# mainBoard.net
KiCad netlist of a schematic drawn in Altium Designer
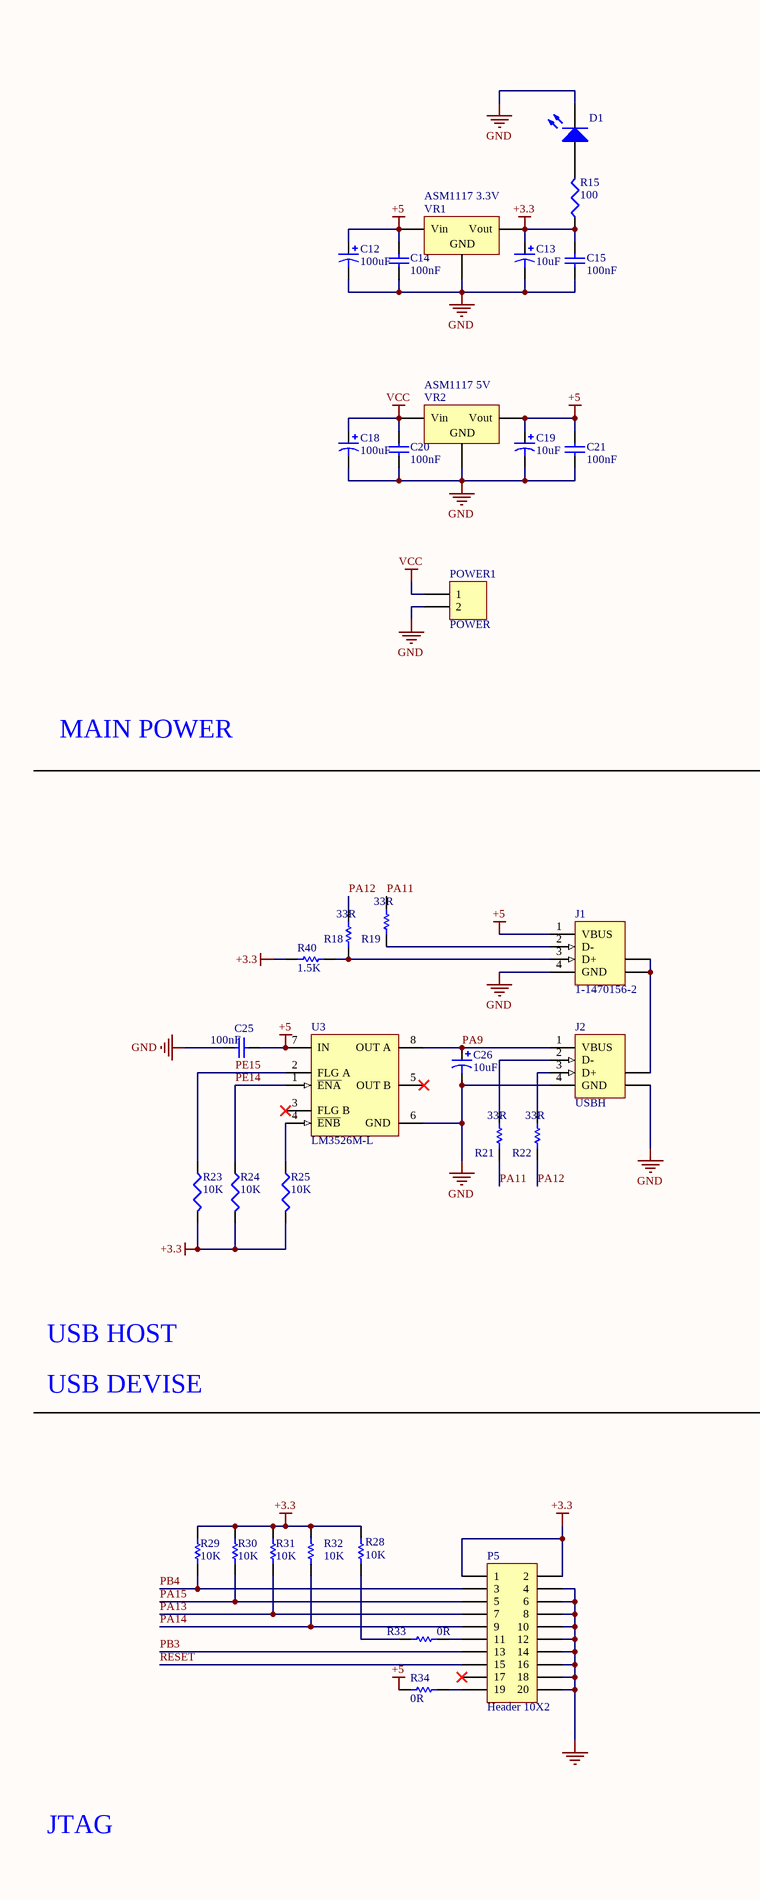
[diagram p0: mainBoard.SchDoc, left]
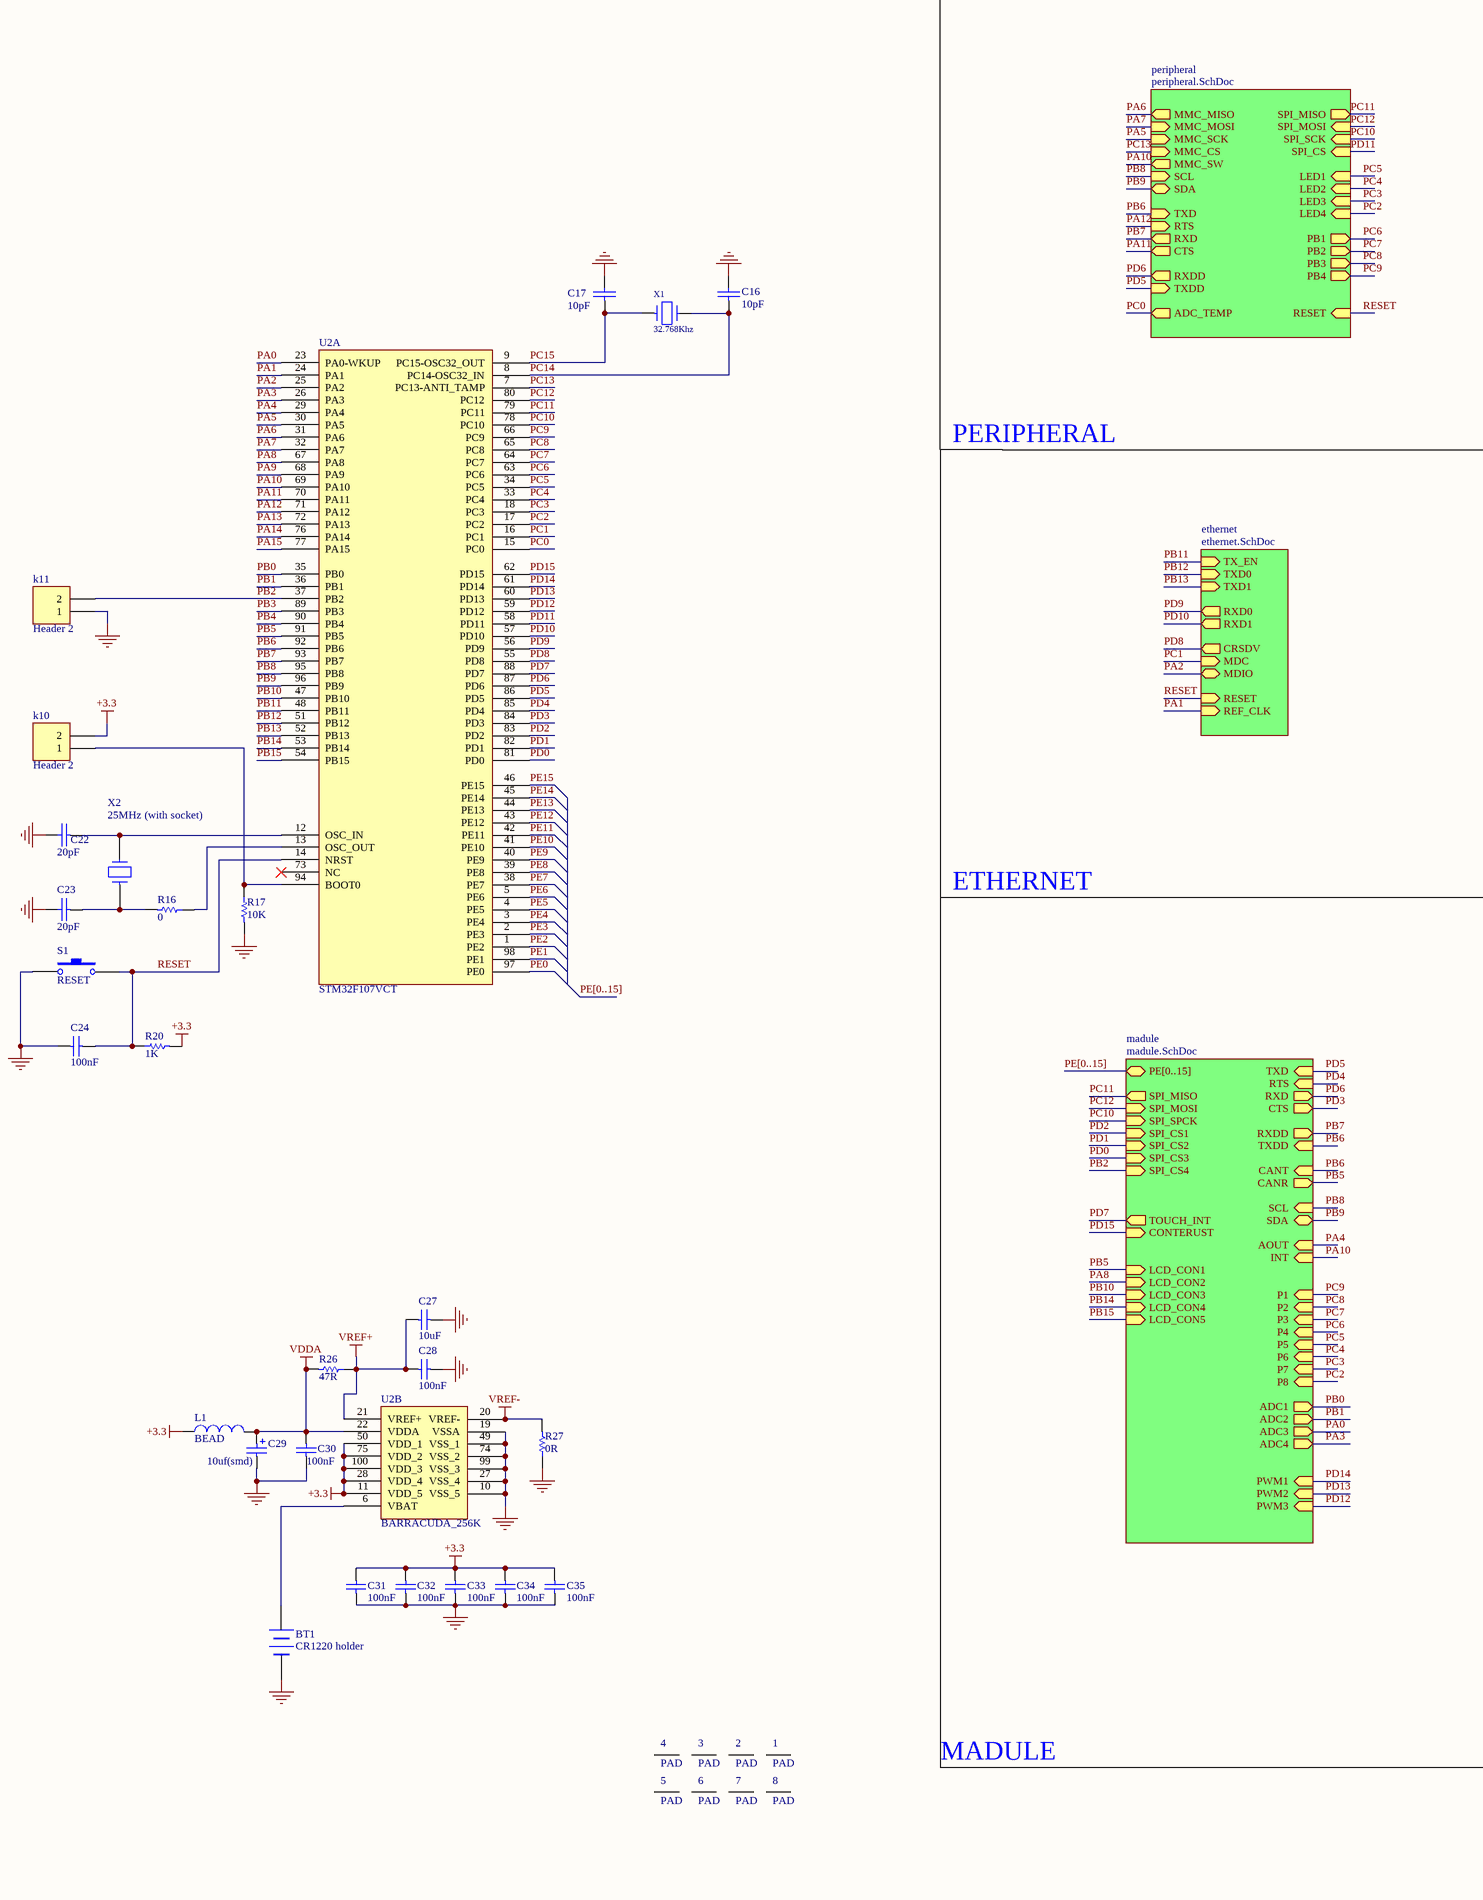
[diagram p1: mainBoard.SchDoc, right]

(export (version "E")
  (design (tool "Eeschema 10.0.6"))
  (components
    (comp (ref "1") (value "PAD") (footprint "pad") (libsource (lib "bobsch") (part "PAD")))
    (comp (ref "2") (value "PAD") (footprint "pad") (libsource (lib "bobsch") (part "PAD")))
    (comp (ref "3") (value "PAD") (footprint "pad") (libsource (lib "bobsch") (part "PAD")))
    (comp (ref "4") (value "PAD") (footprint "pad") (libsource (lib "bobsch") (part "PAD")))
    (comp (ref "5") (value "PAD") (footprint "pad") (libsource (lib "bobsch") (part "PAD")))
    (comp (ref "6") (value "PAD") (footprint "pad") (libsource (lib "bobsch") (part "PAD")))
    (comp (ref "7") (value "PAD") (footprint "pad") (libsource (lib "bobsch") (part "PAD")))
    (comp (ref "8") (value "PAD") (footprint "pad") (libsource (lib "bobsch") (part "PAD")))
    (comp (ref "BT1")
      (value "CR1220 holder")
      (footprint "BAT")
      (description "Battery")
      (libsource (lib "*") (part "BATTERY"))
    )
    (comp (ref "C12")
      (value "100uF")
      (footprint "CAP470")
      (description "Polarized Capacitor (Radial)")
      (fields (field (name "Comment") "100uf") (field (name "PUBLISHER") "Altium Limited"))
      (libsource (lib "Miscellaneous Devices") (part "Cap Pol1"))
    )
    (comp (ref "C13")
      (value "10uF")
      (footprint "CAP10")
      (description "Polarized Capacitor (Radial)")
      (fields (field (name "Comment") "10uf") (field (name "PUBLISHER") "Altium Limited"))
      (libsource (lib "Miscellaneous Devices") (part "Cap Pol1"))
    )
    (comp (ref "C14")
      (value "100nF")
      (footprint "1206")
      (description "Capacitor (Semiconductor SIM Model)")
      (fields (field (name "PUBLISHER") "Altium Limited"))
      (libsource (lib "Miscellaneous Devices") (part "Cap Semi"))
    )
    (comp (ref "C15")
      (value "100nF")
      (footprint "1206")
      (description "Capacitor (Semiconductor SIM Model)")
      (fields (field (name "PUBLISHER") "Altium Limited"))
      (libsource (lib "Miscellaneous Devices") (part "Cap Semi"))
    )
    (comp (ref "C16")
      (value "10pF")
      (footprint "1206")
      (description "Capacitor")
      (libsource (lib "") (part "CAP_1"))
    )
    (comp (ref "C17")
      (value "10pF")
      (footprint "1206")
      (description "Capacitor")
      (libsource (lib "") (part "CAP_1"))
    )
    (comp (ref "C18")
      (value "100uF")
      (footprint "CAP470")
      (description "Polarized Capacitor (Radial)")
      (fields (field (name "Comment") "100uf") (field (name "PUBLISHER") "Altium Limited"))
      (libsource (lib "Miscellaneous Devices") (part "Cap Pol1"))
    )
    (comp (ref "C19")
      (value "10uF")
      (footprint "CAP10")
      (description "Polarized Capacitor (Radial)")
      (fields (field (name "Comment") "10uf") (field (name "PUBLISHER") "Altium Limited"))
      (libsource (lib "Miscellaneous Devices") (part "Cap Pol1"))
    )
    (comp (ref "C20")
      (value "100nF")
      (footprint "1206")
      (description "Capacitor (Semiconductor SIM Model)")
      (fields (field (name "PUBLISHER") "Altium Limited"))
      (libsource (lib "Miscellaneous Devices") (part "Cap Semi"))
    )
    (comp (ref "C21")
      (value "100nF")
      (footprint "1206")
      (description "Capacitor (Semiconductor SIM Model)")
      (fields (field (name "PUBLISHER") "Altium Limited"))
      (libsource (lib "Miscellaneous Devices") (part "Cap Semi"))
    )
    (comp (ref "C22")
      (value "20pF")
      (footprint "1206")
      (description "Capacitor")
      (libsource (lib "*") (part "CAP"))
    )
    (comp (ref "C23")
      (value "20pF")
      (footprint "1206")
      (description "Capacitor")
      (libsource (lib "*") (part "CAP"))
    )
    (comp (ref "C24")
      (value "100nF")
      (footprint "1206")
      (description "Capacitor")
      (fields (field (name "PUBLISHER") "Altium Limited"))
      (libsource (lib "Miscellaneous Devices") (part "CAP"))
    )
    (comp (ref "C25")
      (value "100nF")
      (footprint "mylib:1206")
      (description "Capacitor")
      (fields (field (name "PUBLISHER") "Altium Limited"))
      (libsource (lib "Miscellaneous Devices") (part "Cap"))
    )
    (comp (ref "C26")
      (value "10uF")
      (footprint "CAP10")
      (description "Polarized Capacitor (Radial)")
      (fields (field (name "Comment") "10uf") (field (name "PUBLISHER") "Altium Limited"))
      (libsource (lib "Miscellaneous Devices") (part "Cap Pol1"))
    )
    (comp (ref "C27")
      (value "10uF")
      (footprint "1206")
      (description "Capacitor")
      (fields (field (name "PUBLISHER") "Altium Limited"))
      (libsource (lib "Miscellaneous Devices") (part "Cap"))
    )
    (comp (ref "C28")
      (value "100nF")
      (footprint "1206")
      (description "Capacitor")
      (fields (field (name "PUBLISHER") "Altium Limited"))
      (libsource (lib "Miscellaneous Devices") (part "Cap"))
    )
    (comp (ref "C29")
      (value "10uf(smd)")
      (footprint "1206")
      (description "Polarized Capacitor (Radial)")
      (fields (field (name "PUBLISHER") "Altium Limited"))
      (libsource (lib "") (part "Cap Pol1_1"))
    )
    (comp (ref "C30")
      (value "100nF")
      (footprint "1206")
      (description "Capacitor")
      (fields (field (name "PUBLISHER") "Altium Limited"))
      (libsource (lib "Miscellaneous Devices") (part "Cap"))
    )
    (comp (ref "C31")
      (value "100nF")
      (footprint "0805")
      (description "Capacitor")
      (fields (field (name "PUBLISHER") "Altium Limited"))
      (libsource (lib "Miscellaneous Devices") (part "Cap"))
    )
    (comp (ref "C32")
      (value "100nF")
      (footprint "0805")
      (description "Capacitor")
      (fields (field (name "PUBLISHER") "Altium Limited"))
      (libsource (lib "Miscellaneous Devices") (part "Cap"))
    )
    (comp (ref "C33")
      (value "100nF")
      (footprint "0805")
      (description "Capacitor")
      (fields (field (name "PUBLISHER") "Altium Limited"))
      (libsource (lib "Miscellaneous Devices") (part "Cap"))
    )
    (comp (ref "C34")
      (value "100nF")
      (footprint "0805")
      (description "Capacitor")
      (fields (field (name "PUBLISHER") "Altium Limited"))
      (libsource (lib "Miscellaneous Devices") (part "Cap"))
    )
    (comp (ref "C35")
      (value "100nF")
      (footprint "0805")
      (description "Capacitor")
      (fields (field (name "PUBLISHER") "Altium Limited"))
      (libsource (lib "Miscellaneous Devices") (part "Cap"))
    )
    (comp (ref "D1")
      (value "LED0")
      (footprint "LED-0805")
      (description "Typical INFRARED GaAs LED")
      (fields (field (name "PUBLISHER") "Altium Limited"))
      (libsource (lib "Miscellaneous Devices") (part "LED0"))
    )
    (comp (ref "J1")
      (value "1-1470156-2")
      (footprint "440247")
      (description "USB 1.1, Right Angle, Thru-Hole, B Type, Receptacle, 4 Position, Black")
      (fields (field (name "PUBLISHER") "Altium Limited"))
      (libsource (lib "AMP Serial Bus USB") (part "1-1470156-2"))
    )
    (comp (ref "J2")
      (value "USBH")
      (footprint "787761")
      (description "USB 1.1, Right Angle, Thru-Hole, A Type, Receptacle, 4 Position, Natural")
      (fields (field (name "PUBLISHER") "Altium Limited"))
      (libsource (lib "AMP Serial Bus USB") (part "787761-3"))
    )
    (comp (ref "k10")
      (value "Header 2")
      (footprint "HDR1X2")
      (description "Header, 2-Pin")
      (fields (field (name "PUBLISHER") "Altium Limited"))
      (libsource (lib "Miscellaneous Connectors") (part "Header 2"))
    )
    (comp (ref "k11")
      (value "Header 2")
      (footprint "HDR1X2")
      (description "Header, 2-Pin")
      (fields (field (name "PUBLISHER") "Altium Limited"))
      (libsource (lib "Miscellaneous Connectors") (part "Header 2"))
    )
    (comp (ref "L1")
      (value "BEAD")
      (footprint "1206")
      (description "Inductor")
      (fields (field (name "PUBLISHER") "Altium Limited"))
      (libsource (lib "Miscellaneous Devices") (part "Inductor"))
    )
    (comp (ref "P5")
      (value "Header 10X2")
      (footprint "IDC20S")
      (description "Header, 10-Pin, Dual row")
      (fields (field (name "PUBLISHER") "Altium Limited"))
      (libsource (lib "Miscellaneous Connectors") (part "Header 10X2"))
    )
    (comp (ref "POWER1")
      (value "POWER")
      (footprint "power jack")
      (description "Header, 2-Pin, Right Angle")
      (fields (field (name "PUBLISHER") "Altium Limited"))
      (libsource (lib "Miscellaneous Connectors") (part "Header 2H"))
    )
    (comp (ref "R15")
      (value "100")
      (footprint "1206")
      (description "Resistor")
      (fields (field (name "PUBLISHER") "Altium Limited"))
      (libsource (lib "Miscellaneous Devices") (part "Res3"))
    )
    (comp (ref "R16")
      (value "0")
      (footprint "1206")
      (description "Resistor")
      (fields (field (name "PUBLISHER") "Altium Limited"))
      (libsource (lib "") (part "Res1_1"))
    )
    (comp (ref "R17")
      (value "10K")
      (footprint "1206")
      (description "Resistor")
      (fields (field (name "PUBLISHER") "Altium Limited"))
      (libsource (lib "Miscellaneous Devices") (part "res1"))
    )
    (comp (ref "R18")
      (value "33R")
      (footprint "1206")
      (description "Resistor")
      (fields (field (name "PUBLISHER") "Altium Limited"))
      (libsource (lib "Miscellaneous Devices") (part "Res1"))
    )
    (comp (ref "R19")
      (value "33R")
      (footprint "1206")
      (description "Resistor")
      (fields (field (name "PUBLISHER") "Altium Limited"))
      (libsource (lib "Miscellaneous Devices") (part "Res1"))
    )
    (comp (ref "R20")
      (value "1K")
      (footprint "1206")
      (description "Resistor")
      (fields (field (name "PUBLISHER") "Altium Limited"))
      (libsource (lib "Miscellaneous Devices") (part "res1"))
    )
    (comp (ref "R21")
      (value "33R")
      (footprint "1206")
      (description "Resistor")
      (fields (field (name "PUBLISHER") "Altium Limited"))
      (libsource (lib "Miscellaneous Devices") (part "Res1"))
    )
    (comp (ref "R22")
      (value "33R")
      (footprint "1206")
      (description "Resistor")
      (fields (field (name "PUBLISHER") "Altium Limited"))
      (libsource (lib "Miscellaneous Devices") (part "Res1"))
    )
    (comp (ref "R23") (value "10K") (footprint "1206") (libsource (lib "*") (part "RES1")))
    (comp (ref "R24") (value "10K") (footprint "1206") (libsource (lib "*") (part "RES1")))
    (comp (ref "R25") (value "10K") (footprint "1206") (libsource (lib "*") (part "RES1")))
    (comp (ref "R26")
      (value "47R")
      (footprint "1206")
      (description "Resistor")
      (fields (field (name "PUBLISHER") "Altium Limited"))
      (libsource (lib "") (part "Res1_1"))
    )
    (comp (ref "R27")
      (value "0R")
      (footprint "1206")
      (description "Resistor")
      (fields (field (name "PUBLISHER") "Altium Limited"))
      (libsource (lib "") (part "Res1_1"))
    )
    (comp (ref "R28")
      (value "10K")
      (footprint "1206")
      (description "Resistor")
      (fields (field (name "PUBLISHER") "Altium Limited"))
      (libsource (lib "") (part "Res1_1"))
    )
    (comp (ref "R29")
      (value "10K")
      (footprint "1206")
      (description "Resistor")
      (fields (field (name "PUBLISHER") "Altium Limited"))
      (libsource (lib "") (part "Res1_1"))
    )
    (comp (ref "R30")
      (value "10K")
      (footprint "1206")
      (description "Resistor")
      (fields (field (name "PUBLISHER") "Altium Limited"))
      (libsource (lib "") (part "Res1_1"))
    )
    (comp (ref "R31")
      (value "10K")
      (footprint "1206")
      (description "Resistor")
      (fields (field (name "PUBLISHER") "Altium Limited"))
      (libsource (lib "") (part "Res1_1"))
    )
    (comp (ref "R32")
      (value "10K")
      (footprint "1206")
      (description "Resistor")
      (fields (field (name "PUBLISHER") "Altium Limited"))
      (libsource (lib "") (part "Res1_1"))
    )
    (comp (ref "R33")
      (value "0R")
      (footprint "1206")
      (description "Resistor")
      (fields (field (name "PUBLISHER") "Altium Limited"))
      (libsource (lib "") (part "Res1_1"))
    )
    (comp (ref "R34")
      (value "0R")
      (footprint "1206")
      (description "Resistor")
      (fields (field (name "PUBLISHER") "Altium Limited"))
      (libsource (lib "") (part "Res1_1"))
    )
    (comp (ref "R40")
      (value "1.5K")
      (footprint "1206")
      (description "Resistor")
      (fields (field (name "PUBLISHER") "Altium Limited"))
      (libsource (lib "Miscellaneous Devices") (part "Res1"))
    )
    (comp (ref "S1")
      (value "RESET")
      (footprint "SWSMD")
      (description "Switch")
      (fields (field (name "PUBLISHER") "Altium Limited"))
      (libsource (lib "Miscellaneous Devices") (part "SW-PB"))
    )
    (comp (ref "U2")
      (value "STM32F107VCT")
      (footprint "TQ100_TOOL")
      (libsource (lib "MB784") (part "BARRACUDA_256K"))
    )
    (comp (ref "U3")
      (value "LM3526M-L")
      (footprint "M08A_N")
      (description "Dual Port USB Power Switch and Over-Current Protection")
      (fields
        (field (name "MANUFACTURER") "National Semiconductor")
        (field (name "DIGIKEYPARTNUMBER") "LM3526M-L-ND")
        (field (name "PUBLISHER") "Altium Limited")
      )
      (libsource (lib "NSC MiscPower") (part "LM3526M-L"))
    )
    (comp (ref "VR1")
      (value "ASM1117 3.3V")
      (footprint "Regolator")
      (description "Voltage Regulator")
      (fields (field (name "PUBLISHER") "Altium Limited"))
      (libsource (lib "Miscellaneous Devices") (part "Volt Reg_1"))
    )
    (comp (ref "VR2")
      (value "ASM1117 5V")
      (footprint "Regolator")
      (description "Voltage Regulator")
      (fields (field (name "PUBLISHER") "Altium Limited"))
      (libsource (lib "Miscellaneous Devices") (part "Volt Reg_1"))
    )
    (comp (ref "X1")
      (value "32.768Khz")
      (footprint "OSCILATOR")
      (description "Crystal")
      (libsource (lib "New Lib") (part "XTAL"))
    )
    (comp (ref "X2")
      (value "25MHz (with socket)")
      (footprint "XTAL3")
      (description "Crystal")
      (libsource (lib "*") (part "CRYSTAL"))
    )
  )
  (nets
    (net (code "1") (name "+3.3") (class "Default")
      (node (ref "C13") (pin "1") (pinfunction "1_1") (pintype "passive"))
      (node (ref "C15") (pin "1") (pinfunction "1_1") (pintype "passive"))
      (node (ref "C31") (pin "1") (pinfunction "1_1") (pintype "passive"))
      (node (ref "C32") (pin "1") (pinfunction "1_1") (pintype "passive"))
      (node (ref "C33") (pin "1") (pinfunction "1_1") (pintype "passive"))
      (node (ref "C34") (pin "1") (pinfunction "1_1") (pintype "passive"))
      (node (ref "C35") (pin "1") (pinfunction "1_1") (pintype "passive"))
      (node (ref "L1") (pin "1") (pinfunction "1_1") (pintype "passive"))
      (node (ref "P5") (pin "1") (pinfunction "1_1") (pintype "passive"))
      (node (ref "P5") (pin "2") (pinfunction "2_2") (pintype "passive"))
      (node (ref "R15") (pin "1") (pinfunction "1_1") (pintype "passive"))
      (node (ref "R20") (pin "2") (pinfunction "2_2") (pintype "passive"))
      (node (ref "R23") (pin "2") (pintype "passive"))
      (node (ref "R24") (pin "2") (pintype "passive"))
      (node (ref "R25") (pin "2") (pintype "passive"))
      (node (ref "R28") (pin "2") (pinfunction "2_2") (pintype "passive"))
      (node (ref "R29") (pin "2") (pinfunction "2_2") (pintype "passive"))
      (node (ref "R30") (pin "2") (pinfunction "2_2") (pintype "passive"))
      (node (ref "R31") (pin "2") (pinfunction "2_2") (pintype "passive"))
      (node (ref "R32") (pin "2") (pinfunction "2_2") (pintype "passive"))
      (node (ref "R40") (pin "1") (pinfunction "1_1") (pintype "passive"))
      (node (ref "U2") (pin "100") (pinfunction "VDD_3_100") (pintype "passive"))
      (node (ref "U2") (pin "11") (pinfunction "VDD_5_11") (pintype "passive"))
      (node (ref "U2") (pin "28") (pinfunction "VDD_4_28") (pintype "passive"))
      (node (ref "U2") (pin "50") (pinfunction "VDD_1_50") (pintype "passive"))
      (node (ref "U2") (pin "75") (pinfunction "VDD_2_75") (pintype "passive"))
      (node (ref "VR1") (pin "4") (pinfunction "Vout_4") (pintype "passive"))
      (node (ref "k10") (pin "2") (pinfunction "2_2") (pintype "passive"))
    )
    (net (code "2") (name "+5") (class "Default")
      (node (ref "C12") (pin "1") (pinfunction "1_1") (pintype "passive"))
      (node (ref "C14") (pin "1") (pinfunction "1_1") (pintype "passive"))
      (node (ref "C19") (pin "1") (pinfunction "1_1") (pintype "passive"))
      (node (ref "C21") (pin "1") (pinfunction "1_1") (pintype "passive"))
      (node (ref "C25") (pin "1") (pinfunction "1_1") (pintype "passive"))
      (node (ref "J1") (pin "1") (pinfunction "VBUS_1") (pintype "power_in"))
      (node (ref "R34") (pin "2") (pinfunction "2_2") (pintype "passive"))
      (node (ref "U3") (pin "7") (pinfunction "IN_7") (pintype "power_in"))
      (node (ref "VR1") (pin "3") (pinfunction "Vin_3") (pintype "passive"))
      (node (ref "VR2") (pin "4") (pinfunction "Vout_4") (pintype "passive"))
    )
    (net (code "3") (name "/PA0") (class "Default")
      (node (ref "U2") (pin "23") (pinfunction "PA0-WKUP_23") (pintype "passive"))
    )
    (net (code "4") (name "/PA1") (class "Default")
      (node (ref "U2") (pin "24") (pinfunction "PA1_24") (pintype "passive"))
    )
    (net (code "5") (name "/PA2") (class "Default")
      (node (ref "U2") (pin "25") (pinfunction "PA2_25") (pintype "passive"))
    )
    (net (code "6") (name "/PA3") (class "Default")
      (node (ref "U2") (pin "26") (pinfunction "PA3_26") (pintype "passive"))
    )
    (net (code "7") (name "/PA4") (class "Default")
      (node (ref "U2") (pin "29") (pinfunction "PA4_29") (pintype "passive"))
    )
    (net (code "8") (name "/PA5") (class "Default")
      (node (ref "U2") (pin "30") (pinfunction "PA5_30") (pintype "passive"))
    )
    (net (code "9") (name "/PA6") (class "Default")
      (node (ref "U2") (pin "31") (pinfunction "PA6_31") (pintype "passive"))
    )
    (net (code "10") (name "/PA7") (class "Default")
      (node (ref "U2") (pin "32") (pinfunction "PA7_32") (pintype "passive"))
    )
    (net (code "11") (name "/PA8") (class "Default")
      (node (ref "U2") (pin "67") (pinfunction "PA8_67") (pintype "passive"))
    )
    (net (code "12") (name "/PA9") (class "Default")
      (node (ref "C26") (pin "1") (pinfunction "1_1") (pintype "passive"))
      (node (ref "J2") (pin "1") (pinfunction "VBUS_1") (pintype "power_in"))
      (node (ref "U2") (pin "68") (pinfunction "PA9_68") (pintype "passive"))
      (node (ref "U3") (pin "8") (pinfunction "OUT_A_8") (pintype "power_in"))
    )
    (net (code "13") (name "/PA10") (class "Default")
      (node (ref "U2") (pin "69") (pinfunction "PA10_69") (pintype "passive"))
    )
    (net (code "14") (name "/PA11") (class "Default")
      (node (ref "R19") (pin "1") (pinfunction "1_1") (pintype "passive"))
      (node (ref "R21") (pin "2") (pinfunction "2_2") (pintype "passive"))
      (node (ref "U2") (pin "70") (pinfunction "PA11_70") (pintype "passive"))
    )
    (net (code "15") (name "/PA12") (class "Default")
      (node (ref "R18") (pin "1") (pinfunction "1_1") (pintype "passive"))
      (node (ref "R22") (pin "2") (pinfunction "2_2") (pintype "passive"))
      (node (ref "U2") (pin "71") (pinfunction "PA12_71") (pintype "passive"))
    )
    (net (code "16") (name "/PA13") (class "Default")
      (node (ref "P5") (pin "7") (pinfunction "7_7") (pintype "passive"))
      (node (ref "R31") (pin "1") (pinfunction "1_1") (pintype "passive"))
      (node (ref "U2") (pin "72") (pinfunction "PA13_72") (pintype "passive"))
    )
    (net (code "17") (name "/PA14") (class "Default")
      (node (ref "P5") (pin "9") (pinfunction "9_9") (pintype "passive"))
      (node (ref "R32") (pin "1") (pinfunction "1_1") (pintype "passive"))
      (node (ref "U2") (pin "76") (pinfunction "PA14_76") (pintype "passive"))
    )
    (net (code "18") (name "/PA15") (class "Default")
      (node (ref "P5") (pin "5") (pinfunction "5_5") (pintype "passive"))
      (node (ref "R30") (pin "1") (pinfunction "1_1") (pintype "passive"))
      (node (ref "U2") (pin "77") (pinfunction "PA15_77") (pintype "passive"))
    )
    (net (code "19") (name "/PB0") (class "Default")
      (node (ref "U2") (pin "35") (pinfunction "PB0_35") (pintype "passive"))
    )
    (net (code "20") (name "/PB1") (class "Default")
      (node (ref "U2") (pin "36") (pinfunction "PB1_36") (pintype "passive"))
    )
    (net (code "21") (name "/PB2") (class "Default")
      (node (ref "U2") (pin "37") (pinfunction "PB2_37") (pintype "passive"))
      (node (ref "k11") (pin "2") (pinfunction "2_2") (pintype "passive"))
    )
    (net (code "22") (name "/PB3") (class "Default")
      (node (ref "P5") (pin "13") (pinfunction "13_13") (pintype "passive"))
      (node (ref "U2") (pin "89") (pinfunction "PB3_89") (pintype "passive"))
    )
    (net (code "23") (name "/PB4") (class "Default")
      (node (ref "P5") (pin "3") (pinfunction "3_3") (pintype "passive"))
      (node (ref "R29") (pin "1") (pinfunction "1_1") (pintype "passive"))
      (node (ref "U2") (pin "90") (pinfunction "PB4_90") (pintype "passive"))
    )
    (net (code "24") (name "/PB5") (class "Default")
      (node (ref "U2") (pin "91") (pinfunction "PB5_91") (pintype "passive"))
    )
    (net (code "25") (name "/PB6") (class "Default")
      (node (ref "U2") (pin "92") (pinfunction "PB6_92") (pintype "passive"))
    )
    (net (code "26") (name "/PB7") (class "Default")
      (node (ref "U2") (pin "93") (pinfunction "PB7_93") (pintype "passive"))
    )
    (net (code "27") (name "/PB8") (class "Default")
      (node (ref "U2") (pin "95") (pinfunction "PB8_95") (pintype "passive"))
    )
    (net (code "28") (name "/PB9") (class "Default")
      (node (ref "U2") (pin "96") (pinfunction "PB9_96") (pintype "passive"))
    )
    (net (code "29") (name "/PB10") (class "Default")
      (node (ref "U2") (pin "47") (pinfunction "PB10_47") (pintype "passive"))
    )
    (net (code "30") (name "/PB11") (class "Default")
      (node (ref "U2") (pin "48") (pinfunction "PB11_48") (pintype "passive"))
    )
    (net (code "31") (name "/PB12") (class "Default")
      (node (ref "U2") (pin "51") (pinfunction "PB12_51") (pintype "passive"))
    )
    (net (code "32") (name "/PB13") (class "Default")
      (node (ref "U2") (pin "52") (pinfunction "PB13_52") (pintype "passive"))
    )
    (net (code "33") (name "/PB14") (class "Default")
      (node (ref "U2") (pin "53") (pinfunction "PB14_53") (pintype "passive"))
    )
    (net (code "34") (name "/PB15") (class "Default")
      (node (ref "U2") (pin "54") (pinfunction "PB15_54") (pintype "passive"))
    )
    (net (code "35") (name "/PC0") (class "Default")
      (node (ref "U2") (pin "15") (pinfunction "PC0_15") (pintype "passive"))
    )
    (net (code "36") (name "/PC1") (class "Default")
      (node (ref "U2") (pin "16") (pinfunction "PC1_16") (pintype "passive"))
    )
    (net (code "37") (name "/PC2") (class "Default")
      (node (ref "U2") (pin "17") (pinfunction "PC2_17") (pintype "passive"))
    )
    (net (code "38") (name "/PC3") (class "Default")
      (node (ref "U2") (pin "18") (pinfunction "PC3_18") (pintype "passive"))
    )
    (net (code "39") (name "/PC4") (class "Default")
      (node (ref "U2") (pin "33") (pinfunction "PC4_33") (pintype "passive"))
    )
    (net (code "40") (name "/PC5") (class "Default")
      (node (ref "U2") (pin "34") (pinfunction "PC5_34") (pintype "passive"))
    )
    (net (code "41") (name "/PC6") (class "Default")
      (node (ref "U2") (pin "63") (pinfunction "PC6_63") (pintype "passive"))
    )
    (net (code "42") (name "/PC7") (class "Default")
      (node (ref "U2") (pin "64") (pinfunction "PC7_64") (pintype "passive"))
    )
    (net (code "43") (name "/PC8") (class "Default")
      (node (ref "U2") (pin "65") (pinfunction "PC8_65") (pintype "passive"))
    )
    (net (code "44") (name "/PC9") (class "Default")
      (node (ref "U2") (pin "66") (pinfunction "PC9_66") (pintype "passive"))
    )
    (net (code "45") (name "/PC10") (class "Default")
      (node (ref "U2") (pin "78") (pinfunction "PC10_78") (pintype "passive"))
    )
    (net (code "46") (name "/PC11") (class "Default")
      (node (ref "U2") (pin "79") (pinfunction "PC11_79") (pintype "passive"))
    )
    (net (code "47") (name "/PC12") (class "Default")
      (node (ref "U2") (pin "80") (pinfunction "PC12_80") (pintype "passive"))
    )
    (net (code "48") (name "/PC13") (class "Default")
      (node (ref "U2") (pin "7") (pinfunction "PC13-ANTI_TAMP_7") (pintype "passive"))
    )
    (net (code "49") (name "/PC14") (class "Default")
      (node (ref "C16") (pin "1") (pinfunction "1_1") (pintype "passive"))
      (node (ref "U2") (pin "8") (pinfunction "PC14-OSC32_IN_8") (pintype "passive"))
      (node (ref "X1") (pin "2") (pinfunction "2_2") (pintype "passive"))
    )
    (net (code "50") (name "/PC15") (class "Default")
      (node (ref "C17") (pin "1") (pinfunction "1_1") (pintype "passive"))
      (node (ref "U2") (pin "9") (pinfunction "PC15-OSC32_OUT_9") (pintype "passive"))
      (node (ref "X1") (pin "1") (pinfunction "1_1") (pintype "passive"))
    )
    (net (code "51") (name "/PD0") (class "Default")
      (node (ref "U2") (pin "81") (pinfunction "PD0_81") (pintype "passive"))
    )
    (net (code "52") (name "/PD1") (class "Default")
      (node (ref "U2") (pin "82") (pinfunction "PD1_82") (pintype "passive"))
    )
    (net (code "53") (name "/PD2") (class "Default")
      (node (ref "U2") (pin "83") (pinfunction "PD2_83") (pintype "passive"))
    )
    (net (code "54") (name "/PD3") (class "Default")
      (node (ref "U2") (pin "84") (pinfunction "PD3_84") (pintype "passive"))
    )
    (net (code "55") (name "/PD4") (class "Default")
      (node (ref "U2") (pin "85") (pinfunction "PD4_85") (pintype "passive"))
    )
    (net (code "56") (name "/PD5") (class "Default")
      (node (ref "U2") (pin "86") (pinfunction "PD5_86") (pintype "passive"))
    )
    (net (code "57") (name "/PD6") (class "Default")
      (node (ref "U2") (pin "87") (pinfunction "PD6_87") (pintype "passive"))
    )
    (net (code "58") (name "/PD7") (class "Default")
      (node (ref "U2") (pin "88") (pinfunction "PD7_88") (pintype "passive"))
    )
    (net (code "59") (name "/PD8") (class "Default")
      (node (ref "U2") (pin "55") (pinfunction "PD8_55") (pintype "passive"))
    )
    (net (code "60") (name "/PD9") (class "Default")
      (node (ref "U2") (pin "56") (pinfunction "PD9_56") (pintype "passive"))
    )
    (net (code "61") (name "/PD10") (class "Default")
      (node (ref "U2") (pin "57") (pinfunction "PD10_57") (pintype "passive"))
    )
    (net (code "62") (name "/PD11") (class "Default")
      (node (ref "U2") (pin "58") (pinfunction "PD11_58") (pintype "passive"))
    )
    (net (code "63") (name "/PD12") (class "Default")
      (node (ref "U2") (pin "59") (pinfunction "PD12_59") (pintype "passive"))
    )
    (net (code "64") (name "/PD13") (class "Default")
      (node (ref "U2") (pin "60") (pinfunction "PD13_60") (pintype "passive"))
    )
    (net (code "65") (name "/PD14") (class "Default")
      (node (ref "U2") (pin "61") (pinfunction "PD14_61") (pintype "passive"))
    )
    (net (code "66") (name "/PD15") (class "Default")
      (node (ref "U2") (pin "62") (pinfunction "PD15_62") (pintype "passive"))
    )
    (net (code "67") (name "/PE0") (class "Default")
      (node (ref "U2") (pin "97") (pinfunction "PE0_97") (pintype "passive"))
    )
    (net (code "68") (name "/PE1") (class "Default")
      (node (ref "U2") (pin "98") (pinfunction "PE1_98") (pintype "passive"))
    )
    (net (code "69") (name "/PE2") (class "Default")
      (node (ref "U2") (pin "1") (pinfunction "PE2_1") (pintype "passive"))
    )
    (net (code "70") (name "/PE3") (class "Default")
      (node (ref "U2") (pin "2") (pinfunction "PE3_2") (pintype "passive"))
    )
    (net (code "71") (name "/PE4") (class "Default")
      (node (ref "U2") (pin "3") (pinfunction "PE4_3") (pintype "passive"))
    )
    (net (code "72") (name "/PE5") (class "Default")
      (node (ref "U2") (pin "4") (pinfunction "PE5_4") (pintype "passive"))
    )
    (net (code "73") (name "/PE6") (class "Default")
      (node (ref "U2") (pin "5") (pinfunction "PE6_5") (pintype "passive"))
    )
    (net (code "74") (name "/PE7") (class "Default")
      (node (ref "U2") (pin "38") (pinfunction "PE7_38") (pintype "passive"))
    )
    (net (code "75") (name "/PE8") (class "Default")
      (node (ref "U2") (pin "39") (pinfunction "PE8_39") (pintype "passive"))
    )
    (net (code "76") (name "/PE9") (class "Default")
      (node (ref "U2") (pin "40") (pinfunction "PE9_40") (pintype "passive"))
    )
    (net (code "77") (name "/PE10") (class "Default")
      (node (ref "U2") (pin "41") (pinfunction "PE10_41") (pintype "passive"))
    )
    (net (code "78") (name "/PE11") (class "Default")
      (node (ref "U2") (pin "42") (pinfunction "PE11_42") (pintype "passive"))
    )
    (net (code "79") (name "/PE12") (class "Default")
      (node (ref "U2") (pin "43") (pinfunction "PE12_43") (pintype "passive"))
    )
    (net (code "80") (name "/PE13") (class "Default")
      (node (ref "U2") (pin "44") (pinfunction "PE13_44") (pintype "passive"))
    )
    (net (code "81") (name "/PE14") (class "Default")
      (node (ref "R24") (pin "1") (pintype "passive"))
      (node (ref "U2") (pin "45") (pinfunction "PE14_45") (pintype "passive"))
      (node (ref "U3") (pin "1") (pinfunction "~{ENA}_1") (pintype "input"))
    )
    (net (code "82") (name "/PE15") (class "Default")
      (node (ref "R23") (pin "1") (pintype "passive"))
      (node (ref "U2") (pin "46") (pinfunction "PE15_46") (pintype "passive"))
      (node (ref "U3") (pin "2") (pinfunction "FLG_A_2") (pintype "open_collector"))
    )
    (net (code "84") (name "/RESET") (class "Default")
      (node (ref "C24") (pin "2") (pinfunction "2_2") (pintype "passive"))
      (node (ref "P5") (pin "15") (pinfunction "15_15") (pintype "passive"))
      (node (ref "R20") (pin "1") (pinfunction "1_1") (pintype "passive"))
      (node (ref "S1") (pin "2") (pinfunction "2_2") (pintype "passive"))
      (node (ref "U2") (pin "14") (pinfunction "NRST_14") (pintype "passive"))
    )
    (net (code "85") (name "GND") (class "Default")
      (node (ref "BT1") (pin "2") (pinfunction "-_2") (pintype "passive"))
      (node (ref "C12") (pin "2") (pinfunction "2_2") (pintype "passive"))
      (node (ref "C13") (pin "2") (pinfunction "2_2") (pintype "passive"))
      (node (ref "C14") (pin "2") (pinfunction "2_2") (pintype "passive"))
      (node (ref "C15") (pin "2") (pinfunction "2_2") (pintype "passive"))
      (node (ref "C16") (pin "2") (pinfunction "2_2") (pintype "passive"))
      (node (ref "C17") (pin "2") (pinfunction "2_2") (pintype "passive"))
      (node (ref "C18") (pin "2") (pinfunction "2_2") (pintype "passive"))
      (node (ref "C19") (pin "2") (pinfunction "2_2") (pintype "passive"))
      (node (ref "C20") (pin "2") (pinfunction "2_2") (pintype "passive"))
      (node (ref "C21") (pin "2") (pinfunction "2_2") (pintype "passive"))
      (node (ref "C22") (pin "2") (pinfunction "2_2") (pintype "passive"))
      (node (ref "C23") (pin "2") (pinfunction "2_2") (pintype "passive"))
      (node (ref "C24") (pin "1") (pinfunction "1_1") (pintype "passive"))
      (node (ref "C25") (pin "2") (pinfunction "2_2") (pintype "passive"))
      (node (ref "C26") (pin "2") (pinfunction "2_2") (pintype "passive"))
      (node (ref "C27") (pin "2") (pinfunction "2_2") (pintype "passive"))
      (node (ref "C28") (pin "2") (pinfunction "2_2") (pintype "passive"))
      (node (ref "C29") (pin "2") (pinfunction "2_2") (pintype "passive"))
      (node (ref "C30") (pin "2") (pinfunction "2_2") (pintype "passive"))
      (node (ref "C31") (pin "2") (pinfunction "2_2") (pintype "passive"))
      (node (ref "C32") (pin "2") (pinfunction "2_2") (pintype "passive"))
      (node (ref "C33") (pin "2") (pinfunction "2_2") (pintype "passive"))
      (node (ref "C34") (pin "2") (pinfunction "2_2") (pintype "passive"))
      (node (ref "C35") (pin "2") (pinfunction "2_2") (pintype "passive"))
      (node (ref "D1") (pin "2") (pinfunction "K_2") (pintype "passive"))
      (node (ref "J1") (pin "4") (pinfunction "GND_4") (pintype "power_in"))
      (node (ref "J2") (pin "4") (pinfunction "GND_4") (pintype "power_in"))
      (node (ref "J2") (pin "6") (pinfunction "SHLD_6") (pintype "passive"))
      (node (ref "P5") (pin "10") (pinfunction "10_10") (pintype "passive"))
      (node (ref "P5") (pin "12") (pinfunction "12_12") (pintype "passive"))
      (node (ref "P5") (pin "14") (pinfunction "14_14") (pintype "passive"))
      (node (ref "P5") (pin "16") (pinfunction "16_16") (pintype "passive"))
      (node (ref "P5") (pin "18") (pinfunction "18_18") (pintype "passive"))
      (node (ref "P5") (pin "20") (pinfunction "20_20") (pintype "passive"))
      (node (ref "P5") (pin "4") (pinfunction "4_4") (pintype "passive"))
      (node (ref "P5") (pin "6") (pinfunction "6_6") (pintype "passive"))
      (node (ref "P5") (pin "8") (pinfunction "8_8") (pintype "passive"))
      (node (ref "POWER1") (pin "2") (pinfunction "2_2") (pintype "passive"))
      (node (ref "R17") (pin "2") (pinfunction "2_2") (pintype "passive"))
      (node (ref "R27") (pin "1") (pinfunction "1_1") (pintype "passive"))
      (node (ref "S1") (pin "1") (pinfunction "1_1") (pintype "passive"))
      (node (ref "U2") (pin "10") (pinfunction "VSS_5_10") (pintype "passive"))
      (node (ref "U2") (pin "19") (pinfunction "VSSA_19") (pintype "passive"))
      (node (ref "U2") (pin "27") (pinfunction "VSS_4_27") (pintype "passive"))
      (node (ref "U2") (pin "49") (pinfunction "VSS_1_49") (pintype "passive"))
      (node (ref "U2") (pin "74") (pinfunction "VSS_2_74") (pintype "passive"))
      (node (ref "U2") (pin "99") (pinfunction "VSS_3_99") (pintype "passive"))
      (node (ref "U3") (pin "6") (pinfunction "GND_6") (pintype "power_in"))
      (node (ref "VR1") (pin "1") (pinfunction "GND_1") (pintype "passive"))
      (node (ref "VR2") (pin "1") (pinfunction "GND_1") (pintype "passive"))
      (node (ref "k11") (pin "1") (pinfunction "1_1") (pintype "passive"))
    )
    (net (code "86") (name "Net-(BT1-+)") (class "Default")
      (node (ref "BT1") (pin "1") (pinfunction "+_1") (pintype "passive"))
      (node (ref "U2") (pin "6") (pinfunction "VBAT_6") (pintype "passive"))
    )
    (net (code "87") (name "Net-(C23-Pad1)") (class "Default")
      (node (ref "C23") (pin "1") (pinfunction "1_1") (pintype "passive"))
      (node (ref "R16") (pin "2") (pinfunction "2_2") (pintype "passive"))
      (node (ref "X2") (pin "1") (pinfunction "1_1") (pintype "passive"))
    )
    (net (code "88") (name "Net-(D1-A)") (class "Default")
      (node (ref "D1") (pin "1") (pinfunction "A_1") (pintype "passive"))
      (node (ref "R15") (pin "2") (pinfunction "2_2") (pintype "passive"))
    )
    (net (code "89") (name "Net-(J1-D+)") (class "Default")
      (node (ref "J1") (pin "3") (pinfunction "D+_3") (pintype "input"))
      (node (ref "R18") (pin "2") (pinfunction "2_2") (pintype "passive"))
      (node (ref "R40") (pin "2") (pinfunction "2_2") (pintype "passive"))
    )
    (net (code "90") (name "Net-(J1-D-)") (class "Default")
      (node (ref "J1") (pin "2") (pinfunction "D-_2") (pintype "input"))
      (node (ref "R19") (pin "2") (pinfunction "2_2") (pintype "passive"))
    )
    (net (code "91") (name "Net-(J1-SHLD-Pad5)") (class "Default")
      (node (ref "J1") (pin "5") (pinfunction "SHLD_5") (pintype "passive"))
      (node (ref "J1") (pin "6") (pinfunction "SHLD_6") (pintype "passive"))
      (node (ref "J2") (pin "5") (pinfunction "SHLD_5") (pintype "passive"))
    )
    (net (code "92") (name "Net-(J2-D+)") (class "Default")
      (node (ref "J2") (pin "3") (pinfunction "D+_3") (pintype "input"))
      (node (ref "R22") (pin "1") (pinfunction "1_1") (pintype "passive"))
    )
    (net (code "93") (name "Net-(J2-D-)") (class "Default")
      (node (ref "J2") (pin "2") (pinfunction "D-_2") (pintype "input"))
      (node (ref "R21") (pin "1") (pinfunction "1_1") (pintype "passive"))
    )
    (net (code "94") (name "Net-(P5-Pad11)") (class "Default")
      (node (ref "P5") (pin "11") (pinfunction "11_11") (pintype "passive"))
      (node (ref "R33") (pin "1") (pinfunction "1_1") (pintype "passive"))
    )
    (net (code "95") (name "Net-(P5-Pad19)") (class "Default")
      (node (ref "P5") (pin "19") (pinfunction "19_19") (pintype "passive"))
      (node (ref "R34") (pin "1") (pinfunction "1_1") (pintype "passive"))
    )
    (net (code "96") (name "Net-(R28-Pad1)") (class "Default")
      (node (ref "R28") (pin "1") (pinfunction "1_1") (pintype "passive"))
      (node (ref "R33") (pin "2") (pinfunction "2_2") (pintype "passive"))
    )
    (net (code "97") (name "Net-(U2A-BOOT0)") (class "Default")
      (node (ref "R17") (pin "1") (pinfunction "1_1") (pintype "passive"))
      (node (ref "U2") (pin "94") (pinfunction "BOOT0_94") (pintype "passive"))
      (node (ref "k10") (pin "1") (pinfunction "1_1") (pintype "passive"))
    )
    (net (code "98") (name "Net-(U2A-OSC_IN)") (class "Default")
      (node (ref "C22") (pin "1") (pinfunction "1_1") (pintype "passive"))
      (node (ref "U2") (pin "12") (pinfunction "OSC_IN_12") (pintype "passive"))
      (node (ref "X2") (pin "2") (pinfunction "2_2") (pintype "passive"))
    )
    (net (code "99") (name "Net-(U2A-OSC_OUT)") (class "Default")
      (node (ref "R16") (pin "1") (pinfunction "1_1") (pintype "passive"))
      (node (ref "U2") (pin "13") (pinfunction "OSC_OUT_13") (pintype "passive"))
    )
    (net (code "100") (name "Net-(U3-~{ENB})") (class "Default")
      (node (ref "R25") (pin "1") (pintype "passive"))
      (node (ref "U3") (pin "4") (pinfunction "~{ENB}_4") (pintype "input"))
    )
    (net (code "101") (name "VCC") (class "Default")
      (node (ref "C18") (pin "1") (pinfunction "1_1") (pintype "passive"))
      (node (ref "C20") (pin "1") (pinfunction "1_1") (pintype "passive"))
      (node (ref "POWER1") (pin "1") (pinfunction "1_1") (pintype "passive"))
      (node (ref "VR2") (pin "3") (pinfunction "Vin_3") (pintype "passive"))
    )
    (net (code "102") (name "VDDA") (class "Default")
      (node (ref "C29") (pin "1") (pinfunction "1_1") (pintype "passive"))
      (node (ref "C30") (pin "1") (pinfunction "1_1") (pintype "passive"))
      (node (ref "L1") (pin "2") (pinfunction "2_2") (pintype "passive"))
      (node (ref "R26") (pin "2") (pinfunction "2_2") (pintype "passive"))
      (node (ref "U2") (pin "22") (pinfunction "VDDA_22") (pintype "passive"))
    )
    (net (code "103") (name "VREF+") (class "Default")
      (node (ref "C27") (pin "1") (pinfunction "1_1") (pintype "passive"))
      (node (ref "C28") (pin "1") (pinfunction "1_1") (pintype "passive"))
      (node (ref "R26") (pin "1") (pinfunction "1_1") (pintype "passive"))
      (node (ref "U2") (pin "21") (pinfunction "VREF+_21") (pintype "passive"))
    )
    (net (code "104") (name "VREF-") (class "Default")
      (node (ref "R27") (pin "2") (pinfunction "2_2") (pintype "passive"))
      (node (ref "U2") (pin "20") (pinfunction "VREF-_20") (pintype "passive"))
    )
    (net (code "105") (name "unconnected-(1-Pad1)") (class "Default")
      (node (ref "1") (pin "1") (pinfunction "1_1") (pintype "passive"))
    )
    (net (code "106") (name "unconnected-(2-Pad1)") (class "Default")
      (node (ref "2") (pin "1") (pinfunction "1_1") (pintype "passive"))
    )
    (net (code "107") (name "unconnected-(3-Pad1)") (class "Default")
      (node (ref "3") (pin "1") (pinfunction "1_1") (pintype "passive"))
    )
    (net (code "108") (name "unconnected-(4-Pad1)") (class "Default")
      (node (ref "4") (pin "1") (pinfunction "1_1") (pintype "passive"))
    )
    (net (code "109") (name "unconnected-(5-Pad1)") (class "Default")
      (node (ref "5") (pin "1") (pinfunction "1_1") (pintype "passive"))
    )
    (net (code "110") (name "unconnected-(6-Pad1)") (class "Default")
      (node (ref "6") (pin "1") (pinfunction "1_1") (pintype "passive"))
    )
    (net (code "111") (name "unconnected-(7-Pad1)") (class "Default")
      (node (ref "7") (pin "1") (pinfunction "1_1") (pintype "passive"))
    )
    (net (code "112") (name "unconnected-(8-Pad1)") (class "Default")
      (node (ref "8") (pin "1") (pinfunction "1_1") (pintype "passive"))
    )
    (net (code "113") (name "unconnected-(P5-Pad17)") (class "Default")
      (node (ref "P5") (pin "17") (pinfunction "17_17") (pintype "passive+no_connect"))
    )
    (net (code "114") (name "unconnected-(U2A-NC-Pad73)") (class "Default")
      (node (ref "U2") (pin "73") (pinfunction "NC_73") (pintype "passive+no_connect"))
    )
    (net (code "115") (name "unconnected-(U3-FLG_B-Pad3)") (class "Default")
      (node (ref "U3") (pin "3") (pinfunction "FLG_B_3") (pintype "open_collector+no_connect"))
    )
    (net (code "116") (name "unconnected-(U3-OUT_B-Pad5)") (class "Default")
      (node (ref "U3") (pin "5") (pinfunction "OUT_B_5") (pintype "power_in+no_connect"))
    )
  )
)
